# fpga-bank4.net
KiCad netlist of a schematic drawn in Altium Designer
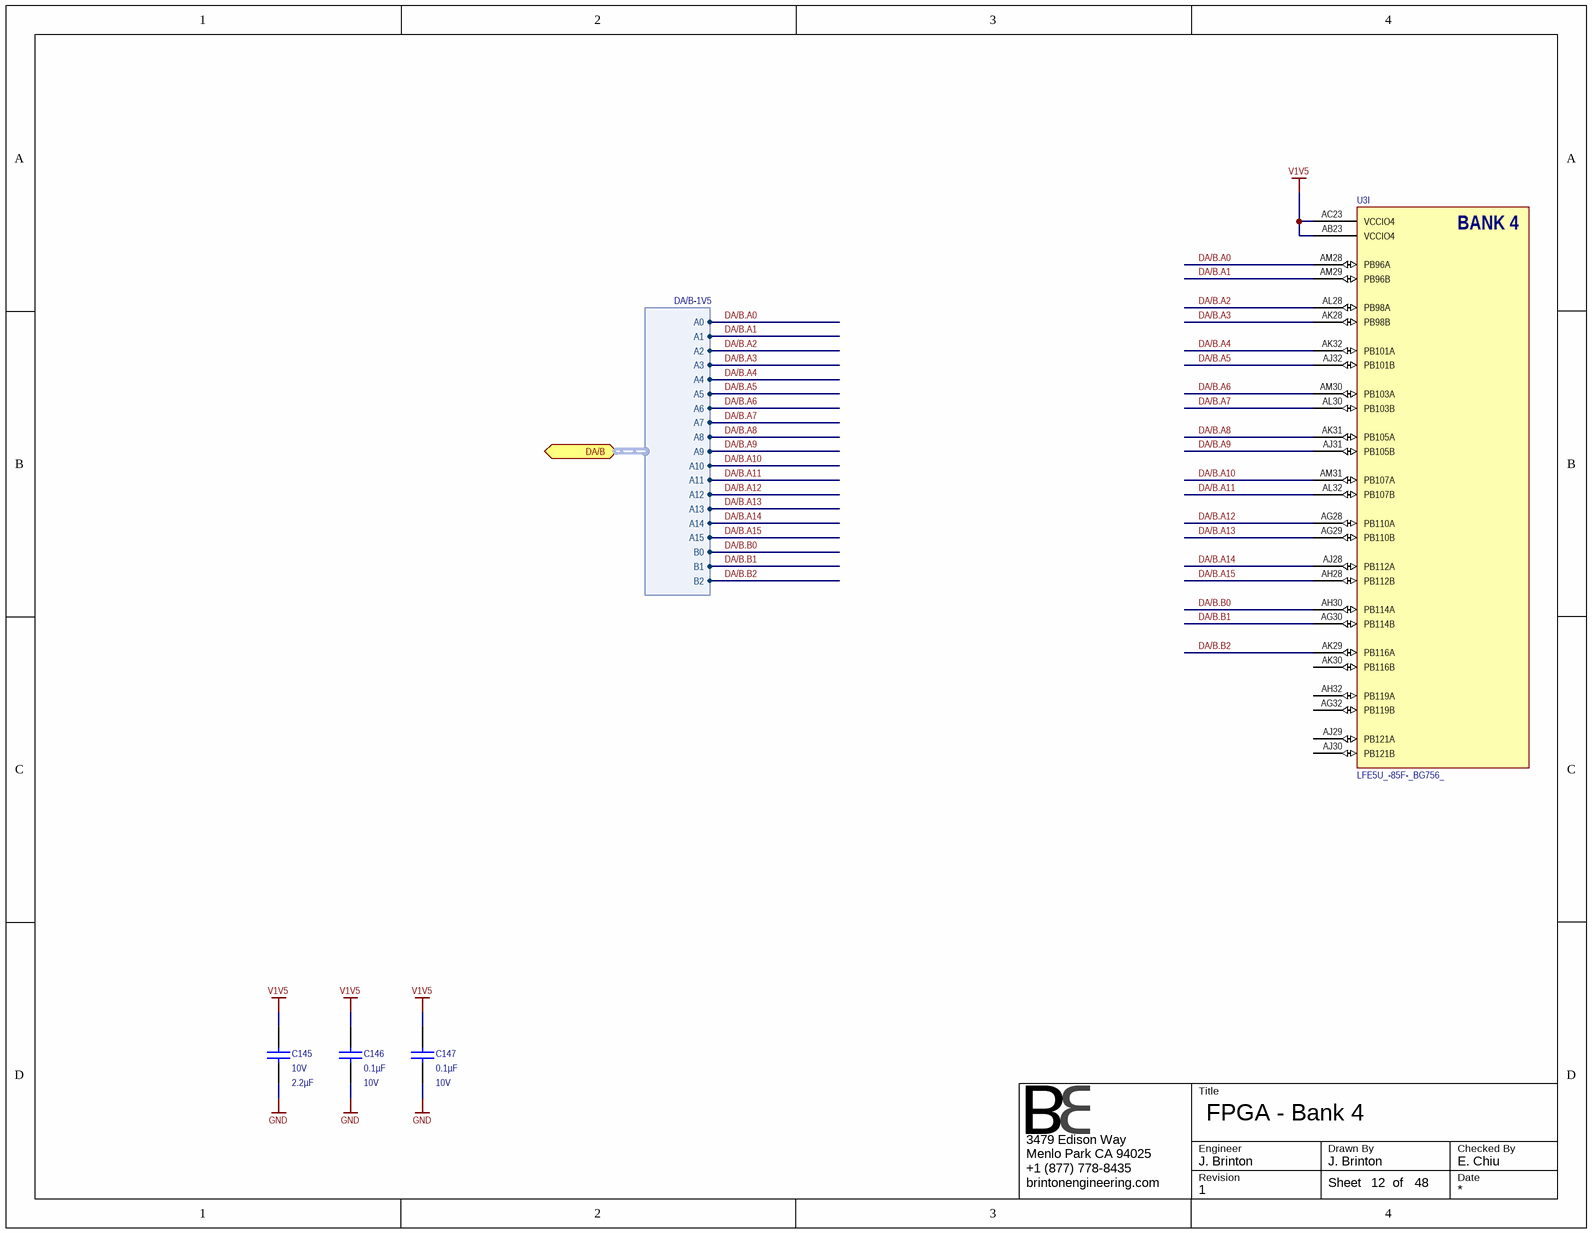
[diagram p0: fpga-bank4.SchDoc]

(export (version "E")
  (design (tool "Eeschema 10.0.6"))
  (components
    (comp (ref "C145")
      (value "GRM188R71A225KE15D")
      (footprint "CAPC1608X90N")
      (description "CAP CER 2.2UF 10V 10% X7R 0603")
      (fields
        (field (name "MANUFACTURER") "Murata Electronics North America")
        (field (name "TOLERANCE") "±10%")
        (field (name "VOLTAGE - RATED") "10V")
        (field (name "CAPACITANCE") "2.2µF")
      )
      (libsource (lib "murata") (part "GRM188R71A225KE15D"))
    )
    (comp (ref "C146")
      (value "GRM155R71A104KA01J")
      (footprint "CAPC1005X56N")
      (description "CAP CER 0.1UF 10V 10% X7R 0402")
      (fields
        (field (name "MANUFACTURER") "Murata Electronics North America")
        (field (name "TOLERANCE") "±10%")
        (field (name "CAPACITANCE") "0.1µF")
        (field (name "VOLTAGE - RATED") "10V")
      )
      (libsource (lib "murata") (part "GRM155R71A104KA01J"))
    )
    (comp (ref "C147")
      (value "GRM155R71A104KA01J")
      (footprint "CAPC1005X56N")
      (description "CAP CER 0.1UF 10V 10% X7R 0402")
      (fields
        (field (name "MANUFACTURER") "Murata Electronics North America")
        (field (name "TOLERANCE") "±10%")
        (field (name "CAPACITANCE") "0.1µF")
        (field (name "VOLTAGE - RATED") "10V")
      )
      (libsource (lib "murata") (part "GRM155R71A104KA01J"))
    )
    (comp (ref "U3")
      (value "LFE5U_-85F-_BG756_")
      (footprint "lattice:caBGA756")
      (description "ECP5 FPGA, 85k LUT, 756-caBGA")
      (fields (field (name "MANUFACTURER") "Lattice Semiconductor"))
      (libsource (lib "lattice") (part "LFE5U_-85F-_BG756_"))
    )
  )
  (nets
    (net (code "2") (name "/DA{slash}B.A0") (class "Default")
      (node (ref "U3") (pin "AM28") (pinfunction "PB96A_AM28") (pintype "bidirectional"))
    )
    (net (code "3") (name "/DA{slash}B.A1") (class "Default")
      (node (ref "U3") (pin "AM29") (pinfunction "PB96B_AM29") (pintype "bidirectional"))
    )
    (net (code "4") (name "/DA{slash}B.A2") (class "Default")
      (node (ref "U3") (pin "AL28") (pinfunction "PB98A_AL28") (pintype "bidirectional"))
    )
    (net (code "5") (name "/DA{slash}B.A3") (class "Default")
      (node (ref "U3") (pin "AK28") (pinfunction "PB98B_AK28") (pintype "bidirectional"))
    )
    (net (code "6") (name "/DA{slash}B.A4") (class "Default")
      (node (ref "U3") (pin "AK32") (pinfunction "PB101A_AK32") (pintype "bidirectional"))
    )
    (net (code "7") (name "/DA{slash}B.A5") (class "Default")
      (node (ref "U3") (pin "AJ32") (pinfunction "PB101B_AJ32") (pintype "bidirectional"))
    )
    (net (code "8") (name "/DA{slash}B.A6") (class "Default")
      (node (ref "U3") (pin "AM30") (pinfunction "PB103A_AM30") (pintype "bidirectional"))
    )
    (net (code "9") (name "/DA{slash}B.A7") (class "Default")
      (node (ref "U3") (pin "AL30") (pinfunction "PB103B_AL30") (pintype "bidirectional"))
    )
    (net (code "10") (name "/DA{slash}B.A8") (class "Default")
      (node (ref "U3") (pin "AK31") (pinfunction "PB105A_AK31") (pintype "bidirectional"))
    )
    (net (code "11") (name "/DA{slash}B.A9") (class "Default")
      (node (ref "U3") (pin "AJ31") (pinfunction "PB105B_AJ31") (pintype "bidirectional"))
    )
    (net (code "12") (name "/DA{slash}B.A10") (class "Default")
      (node (ref "U3") (pin "AM31") (pinfunction "PB107A_AM31") (pintype "bidirectional"))
    )
    (net (code "13") (name "/DA{slash}B.A11") (class "Default")
      (node (ref "U3") (pin "AL32") (pinfunction "PB107B_AL32") (pintype "bidirectional"))
    )
    (net (code "14") (name "/DA{slash}B.A12") (class "Default")
      (node (ref "U3") (pin "AG28") (pinfunction "PB110A_AG28") (pintype "bidirectional"))
    )
    (net (code "15") (name "/DA{slash}B.A13") (class "Default")
      (node (ref "U3") (pin "AG29") (pinfunction "PB110B_AG29") (pintype "bidirectional"))
    )
    (net (code "16") (name "/DA{slash}B.A14") (class "Default")
      (node (ref "U3") (pin "AJ28") (pinfunction "PB112A_AJ28") (pintype "bidirectional"))
    )
    (net (code "17") (name "/DA{slash}B.A15") (class "Default")
      (node (ref "U3") (pin "AH28") (pinfunction "PB112B_AH28") (pintype "bidirectional"))
    )
    (net (code "18") (name "/DA{slash}B.B0") (class "Default")
      (node (ref "U3") (pin "AH30") (pinfunction "PB114A_AH30") (pintype "bidirectional"))
    )
    (net (code "19") (name "/DA{slash}B.B1") (class "Default")
      (node (ref "U3") (pin "AG30") (pinfunction "PB114B_AG30") (pintype "bidirectional"))
    )
    (net (code "20") (name "/DA{slash}B.B2") (class "Default")
      (node (ref "U3") (pin "AK29") (pinfunction "PB116A_AK29") (pintype "bidirectional"))
    )
    (net (code "22") (name "GND") (class "Default")
      (node (ref "C145") (pin "1") (pinfunction "1_1") (pintype "passive"))
      (node (ref "C146") (pin "1") (pinfunction "1_1") (pintype "passive"))
      (node (ref "C147") (pin "1") (pinfunction "1_1") (pintype "passive"))
    )
    (net (code "23") (name "V1V5") (class "Default")
      (node (ref "C145") (pin "2") (pinfunction "2_2") (pintype "passive"))
      (node (ref "C146") (pin "2") (pinfunction "2_2") (pintype "passive"))
      (node (ref "C147") (pin "2") (pinfunction "2_2") (pintype "passive"))
      (node (ref "U3") (pin "AB23") (pinfunction "VCCIO4_AB23") (pintype "power_in"))
      (node (ref "U3") (pin "AC23") (pinfunction "VCCIO4_AC23") (pintype "power_in"))
    )
    (net (code "24") (name "unconnected-(U3I-PB116B-PadAK30)") (class "Default")
      (node (ref "U3") (pin "AK30") (pinfunction "PB116B_AK30") (pintype "bidirectional"))
    )
    (net (code "25") (name "unconnected-(U3I-PB119A-PadAH32)") (class "Default")
      (node (ref "U3") (pin "AH32") (pinfunction "PB119A_AH32") (pintype "bidirectional"))
    )
    (net (code "26") (name "unconnected-(U3I-PB119B-PadAG32)") (class "Default")
      (node (ref "U3") (pin "AG32") (pinfunction "PB119B_AG32") (pintype "bidirectional"))
    )
    (net (code "27") (name "unconnected-(U3I-PB121A-PadAJ29)") (class "Default")
      (node (ref "U3") (pin "AJ29") (pinfunction "PB121A_AJ29") (pintype "bidirectional"))
    )
    (net (code "28") (name "unconnected-(U3I-PB121B-PadAJ30)") (class "Default")
      (node (ref "U3") (pin "AJ30") (pinfunction "PB121B_AJ30") (pintype "bidirectional"))
    )
  )
)
